# bop.net
KiCad netlist of a schematic drawn in EasyEDA Pro
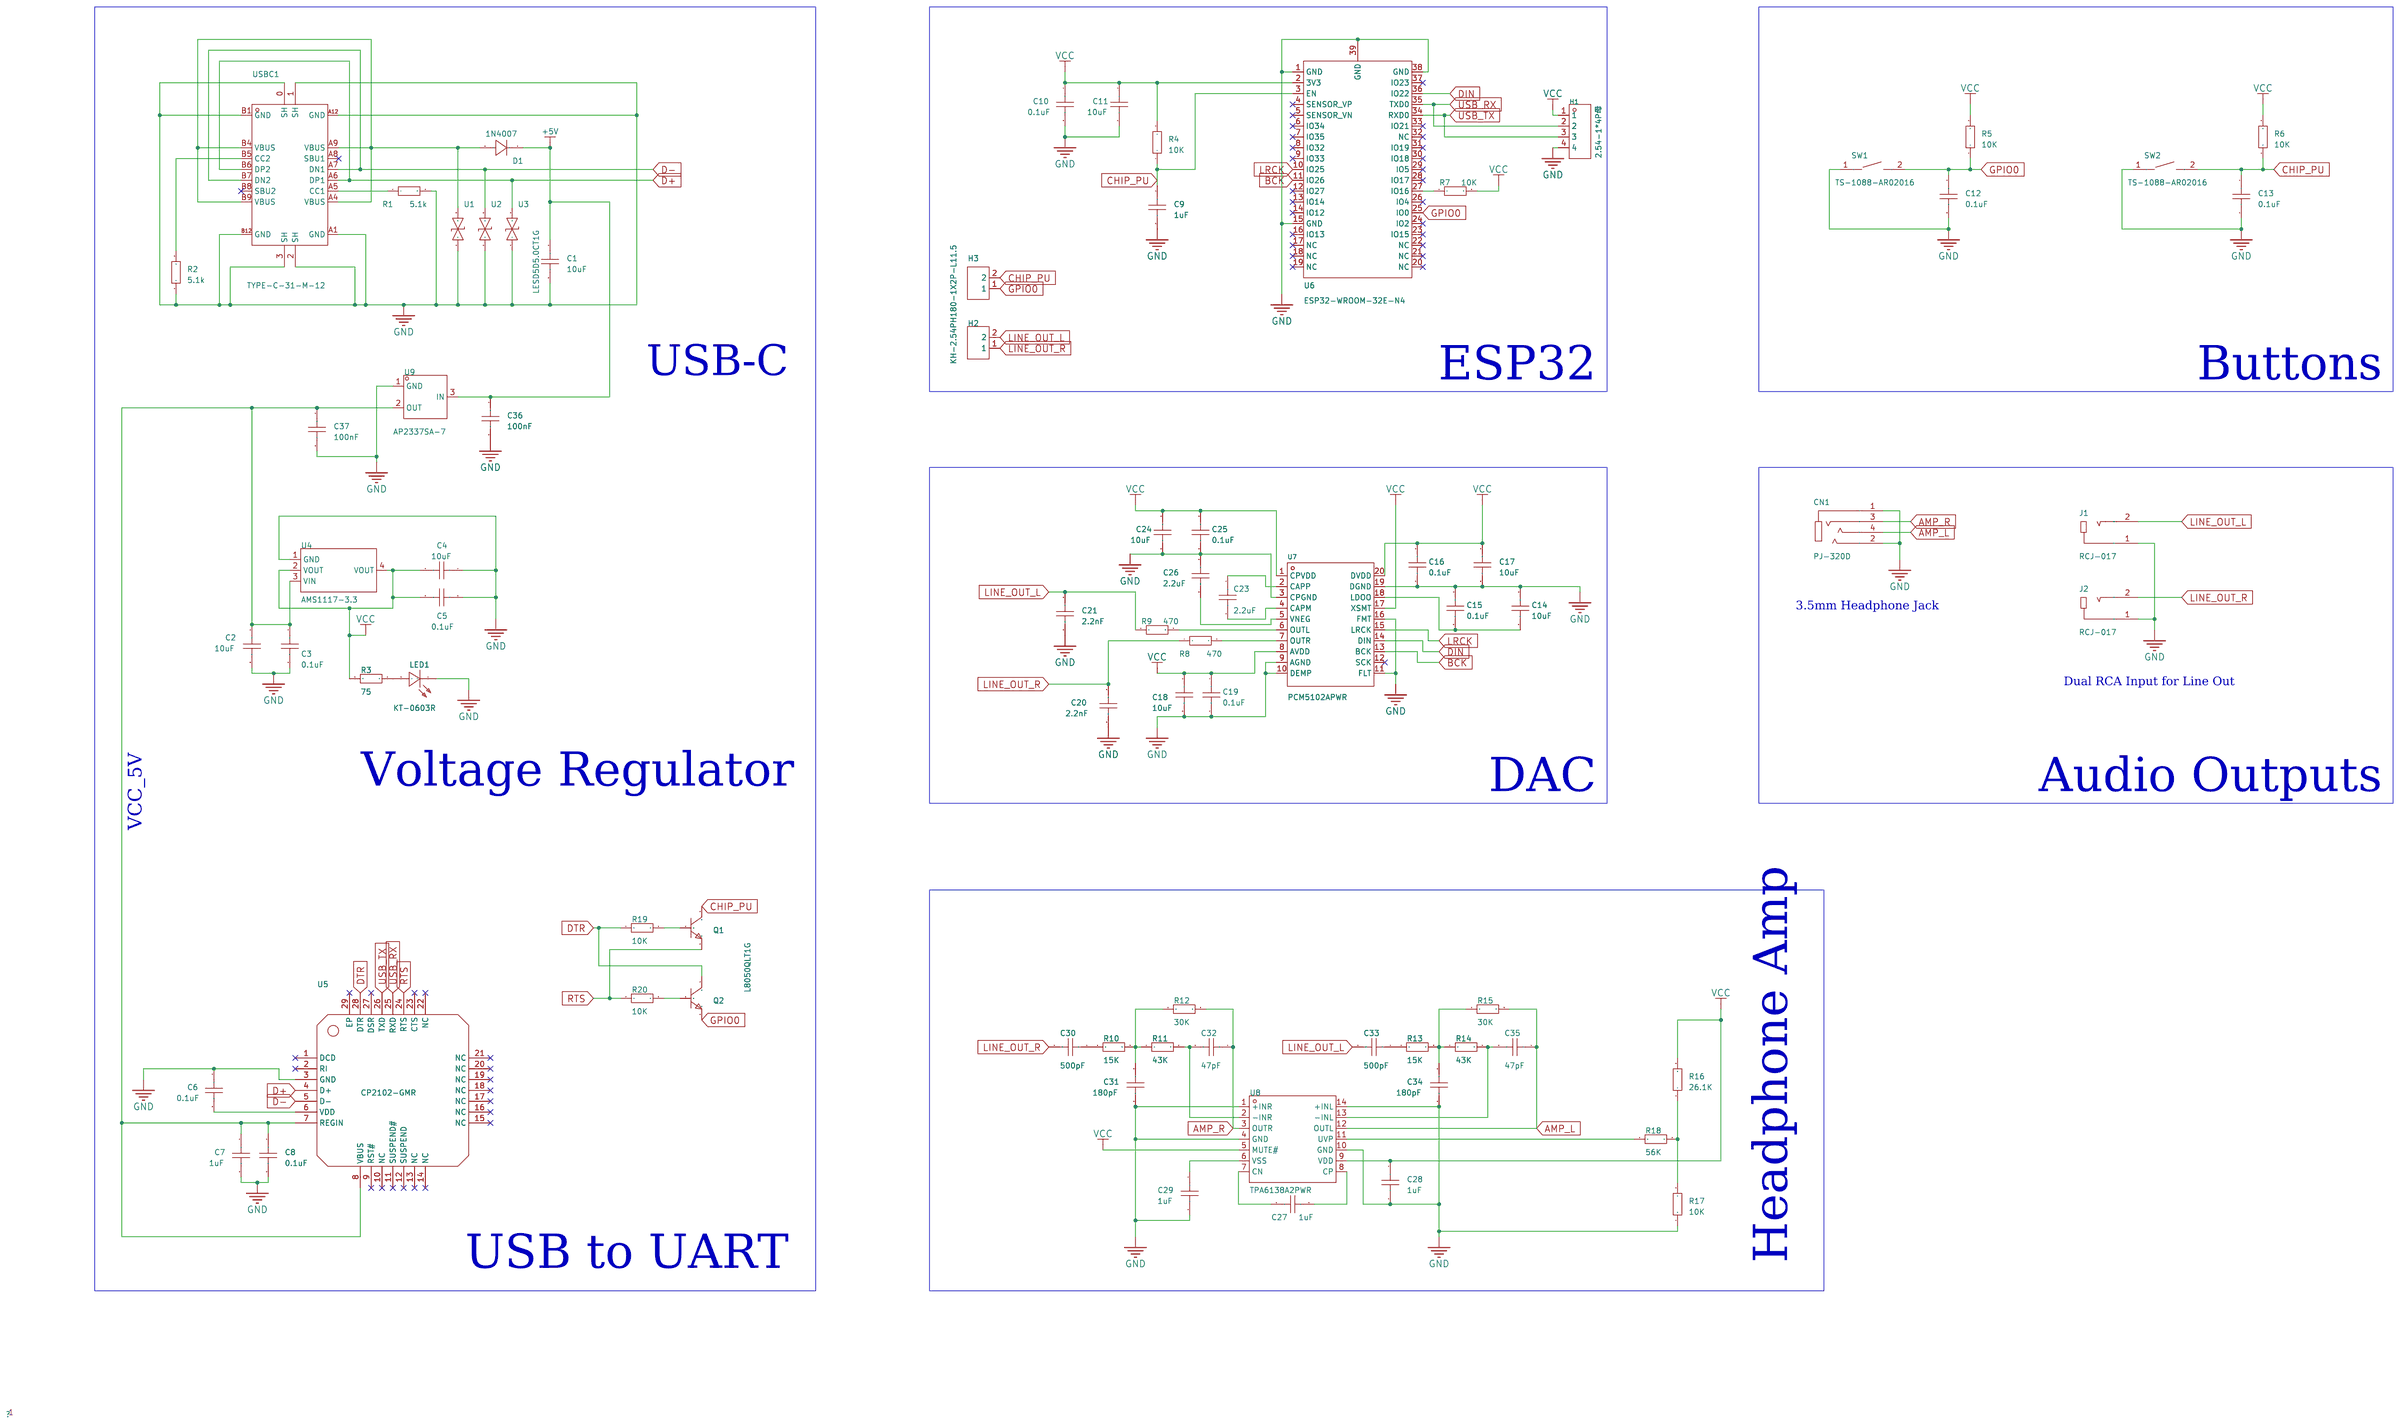
[diagram p0: schematic sheet]

(export (version "E")
  (design (tool "Eeschema 10.0.6"))
  (components
    (comp (ref "C1")
      (value "10uF")
      (footprint "easyedapro:C0603")
      (libsource (lib "easyedapro") (part "CAP"))
    )
    (comp (ref "C2")
      (value "10uF")
      (footprint "easyedapro:C0603")
      (libsource (lib "easyedapro") (part "CAP"))
    )
    (comp (ref "C3")
      (value "0.1uF")
      (footprint "easyedapro:C0603")
      (libsource (lib "easyedapro") (part "CAP"))
    )
    (comp (ref "C4")
      (value "10uF")
      (footprint "easyedapro:C0603")
      (libsource (lib "easyedapro") (part "CAP"))
    )
    (comp (ref "C5")
      (value "0.1uF")
      (footprint "easyedapro:C0603")
      (libsource (lib "easyedapro") (part "CAP"))
    )
    (comp (ref "C6")
      (value "0.1uF")
      (footprint "easyedapro:C0603")
      (libsource (lib "easyedapro") (part "CAP"))
    )
    (comp (ref "C7") (value "1uF") (footprint "easyedapro:C0603") (libsource (lib "easyedapro") (part "CAP")))
    (comp (ref "C8")
      (value "0.1uF")
      (footprint "easyedapro:C0603")
      (libsource (lib "easyedapro") (part "CAP"))
    )
    (comp (ref "C9") (value "1uF") (footprint "easyedapro:C0603") (libsource (lib "easyedapro") (part "CAP")))
    (comp (ref "C10")
      (value "0.1uF")
      (footprint "easyedapro:C0603")
      (libsource (lib "easyedapro") (part "CAP"))
    )
    (comp (ref "C11")
      (value "10uF")
      (footprint "easyedapro:C0603")
      (libsource (lib "easyedapro") (part "CAP"))
    )
    (comp (ref "C12")
      (value "0.1uF")
      (footprint "easyedapro:C0603")
      (libsource (lib "easyedapro") (part "CAP"))
    )
    (comp (ref "C13")
      (value "0.1uF")
      (footprint "easyedapro:C0603")
      (libsource (lib "easyedapro") (part "CAP"))
    )
    (comp (ref "C14")
      (value "10uF")
      (footprint "easyedapro:C0603")
      (libsource (lib "easyedapro") (part "CAP"))
    )
    (comp (ref "C15")
      (value "0.1uF")
      (footprint "easyedapro:C0603")
      (libsource (lib "easyedapro") (part "CAP"))
    )
    (comp (ref "C16")
      (value "0.1uF")
      (footprint "easyedapro:C0603")
      (libsource (lib "easyedapro") (part "CAP"))
    )
    (comp (ref "C17")
      (value "10uF")
      (footprint "easyedapro:C0603")
      (libsource (lib "easyedapro") (part "CAP"))
    )
    (comp (ref "C18")
      (value "10uF")
      (footprint "easyedapro:C0603")
      (libsource (lib "easyedapro") (part "CAP"))
    )
    (comp (ref "C19")
      (value "0.1uF")
      (footprint "easyedapro:C0603")
      (libsource (lib "easyedapro") (part "CAP"))
    )
    (comp (ref "C20")
      (value "2.2nF")
      (footprint "easyedapro:C0603")
      (libsource (lib "easyedapro") (part "CAP"))
    )
    (comp (ref "C21")
      (value "2.2nF")
      (footprint "easyedapro:C0603")
      (libsource (lib "easyedapro") (part "CAP"))
    )
    (comp (ref "C23")
      (value "2.2uF")
      (footprint "easyedapro:C0603")
      (libsource (lib "easyedapro") (part "CAP"))
    )
    (comp (ref "C24")
      (value "10uF")
      (footprint "easyedapro:C0603")
      (libsource (lib "easyedapro") (part "CAP"))
    )
    (comp (ref "C25")
      (value "0.1uF")
      (footprint "easyedapro:C0603")
      (libsource (lib "easyedapro") (part "CAP"))
    )
    (comp (ref "C26")
      (value "2.2uF")
      (footprint "easyedapro:C0603")
      (libsource (lib "easyedapro") (part "CAP"))
    )
    (comp (ref "C27")
      (value "1uF")
      (footprint "easyedapro:C0603")
      (libsource (lib "easyedapro") (part "CAP"))
    )
    (comp (ref "C28")
      (value "1uF")
      (footprint "easyedapro:C0603")
      (libsource (lib "easyedapro") (part "CAP"))
    )
    (comp (ref "C29")
      (value "1uF")
      (footprint "easyedapro:C0603")
      (libsource (lib "easyedapro") (part "CAP"))
    )
    (comp (ref "C30")
      (value "500pF")
      (footprint "easyedapro:C0603")
      (libsource (lib "easyedapro") (part "CAP"))
    )
    (comp (ref "C31")
      (value "180pF")
      (footprint "easyedapro:C0603")
      (libsource (lib "easyedapro") (part "CAP"))
    )
    (comp (ref "C32")
      (value "47pF")
      (footprint "easyedapro:C0603")
      (libsource (lib "easyedapro") (part "CAP"))
    )
    (comp (ref "C33")
      (value "500pF")
      (footprint "easyedapro:C0603")
      (libsource (lib "easyedapro") (part "CAP"))
    )
    (comp (ref "C34")
      (value "180pF")
      (footprint "easyedapro:C0603")
      (libsource (lib "easyedapro") (part "CAP"))
    )
    (comp (ref "C35")
      (value "47pF")
      (footprint "easyedapro:C0603")
      (libsource (lib "easyedapro") (part "CAP"))
    )
    (comp (ref "C36")
      (value "100nF")
      (footprint "easyedapro:C0603")
      (libsource (lib "easyedapro") (part "CAP"))
    )
    (comp (ref "C37")
      (value "100nF")
      (footprint "easyedapro:C0603")
      (libsource (lib "easyedapro") (part "CAP"))
    )
    (comp (ref "CN1")
      (value "PJ-320D")
      (footprint "easyedapro:AUDIO-SMD_PJ-320D")
      (fields (field (name "Manufacturer") "USAKRO(美韩)"))
      (libsource (lib "easyedapro") (part "PJ-320D_C521460"))
    )
    (comp (ref "D1")
      (value "1N4007")
      (footprint "easyedapro:SMA_L4.3-W2.5-LS5.0-RD")
      (fields (field (name "Manufacturer") "TWGMC(台湾迪嘉)"))
      (libsource (lib "easyedapro") (part "1N4007_C727081"))
    )
    (comp (ref "H1")
      (value "2.54-1*4P母")
      (footprint "easyedapro:HDR-TH_4P-P2.54-V-F")
      (fields (field (name "Manufacturer") "BOOMELE(博穆精密)"))
      (libsource (lib "easyedapro") (part "2.54-1*4P母"))
    )
    (comp (ref "H2")
      (value "KH-2.54PH180-1X2P-L11.5")
      (footprint "easyedapro:HDR-TH_2P-P2.54-V-M")
      (fields (field (name "Manufacturer") "kinghelm(金航标)"))
      (libsource (lib "easyedapro") (part "KH-2.54PH180-1X2P-L11.5"))
    )
    (comp (ref "H3")
      (value "KH-2.54PH180-1X2P-L11.5")
      (footprint "easyedapro:HDR-TH_2P-P2.54-V-M")
      (fields (field (name "Manufacturer") "kinghelm(金航标)"))
      (libsource (lib "easyedapro") (part "KH-2.54PH180-1X2P-L11.5"))
    )
    (comp (ref "J1")
      (value "RCJ-017")
      (footprint "easyedapro:CONN-TH_RCJ-013")
      (fields (field (name "Manufacturer") "CUI"))
      (libsource (lib "easyedapro") (part "RCJ-017"))
    )
    (comp (ref "J2")
      (value "RCJ-017")
      (footprint "easyedapro:CONN-TH_RCJ-013")
      (fields (field (name "Manufacturer") "CUI"))
      (libsource (lib "easyedapro") (part "RCJ-017"))
    )
    (comp (ref "LED1")
      (value "KT-0603R")
      (footprint "easyedapro:LED0603-RD")
      (fields (field (name "Manufacturer") "KENTO"))
      (libsource (lib "easyedapro") (part "KT-0603R"))
    )
    (comp (ref "Q1")
      (value "L8050QLT1G")
      (footprint "easyedapro:SOT-23-3_L2.9-W1.3-P1.90-LS2.4-BR")
      (fields (field (name "Manufacturer") "LRC(乐山无线电)"))
      (libsource (lib "easyedapro") (part "L8050QLT1G"))
    )
    (comp (ref "Q2")
      (value "L8050QLT1G")
      (footprint "easyedapro:SOT-23-3_L2.9-W1.3-P1.90-LS2.4-BR")
      (fields (field (name "Manufacturer") "LRC(乐山无线电)"))
      (libsource (lib "easyedapro") (part "L8050QLT1G"))
    )
    (comp (ref "R1")
      (value "5.1k")
      (footprint "easyedapro:R0603")
      (libsource (lib "easyedapro") (part "Res"))
    )
    (comp (ref "R2")
      (value "5.1k")
      (footprint "easyedapro:R0603")
      (libsource (lib "easyedapro") (part "Res"))
    )
    (comp (ref "R3") (value "75") (footprint "easyedapro:R0603") (libsource (lib "easyedapro") (part "Res")))
    (comp (ref "R4") (value "10K") (footprint "easyedapro:R0603") (libsource (lib "easyedapro") (part "Res")))
    (comp (ref "R5") (value "10K") (footprint "easyedapro:R0603") (libsource (lib "easyedapro") (part "Res")))
    (comp (ref "R6") (value "10K") (footprint "easyedapro:R0603") (libsource (lib "easyedapro") (part "Res")))
    (comp (ref "R7") (value "10K") (footprint "easyedapro:R0603") (libsource (lib "easyedapro") (part "Res")))
    (comp (ref "R8") (value "470") (footprint "easyedapro:R0603") (libsource (lib "easyedapro") (part "Res")))
    (comp (ref "R9") (value "470") (footprint "easyedapro:R0603") (libsource (lib "easyedapro") (part "Res")))
    (comp (ref "R10")
      (value "15K")
      (footprint "easyedapro:R0603")
      (libsource (lib "easyedapro") (part "Res"))
    )
    (comp (ref "R11")
      (value "43K")
      (footprint "easyedapro:R0603")
      (libsource (lib "easyedapro") (part "Res"))
    )
    (comp (ref "R12")
      (value "30K")
      (footprint "easyedapro:R0603")
      (libsource (lib "easyedapro") (part "Res"))
    )
    (comp (ref "R13")
      (value "15K")
      (footprint "easyedapro:R0603")
      (libsource (lib "easyedapro") (part "Res"))
    )
    (comp (ref "R14")
      (value "43K")
      (footprint "easyedapro:R0603")
      (libsource (lib "easyedapro") (part "Res"))
    )
    (comp (ref "R15")
      (value "30K")
      (footprint "easyedapro:R0603")
      (libsource (lib "easyedapro") (part "Res"))
    )
    (comp (ref "R16")
      (value "26.1K")
      (footprint "easyedapro:R0603")
      (libsource (lib "easyedapro") (part "Res"))
    )
    (comp (ref "R17")
      (value "10K")
      (footprint "easyedapro:R0603")
      (libsource (lib "easyedapro") (part "Res"))
    )
    (comp (ref "R18")
      (value "56K")
      (footprint "easyedapro:R0603")
      (libsource (lib "easyedapro") (part "Res"))
    )
    (comp (ref "R19")
      (value "10K")
      (footprint "easyedapro:R0603")
      (libsource (lib "easyedapro") (part "Res"))
    )
    (comp (ref "R20")
      (value "10K")
      (footprint "easyedapro:R0603")
      (libsource (lib "easyedapro") (part "Res"))
    )
    (comp (ref "SW1")
      (value "TS-1088-AR02016")
      (footprint "easyedapro:SW-SMD_L3.9-W3.0-P4.45")
      (fields (field (name "Manufacturer") "XUNPU(讯普)"))
      (libsource (lib "easyedapro") (part "TS-1088-AR02016"))
    )
    (comp (ref "SW2")
      (value "TS-1088-AR02016")
      (footprint "easyedapro:SW-SMD_L3.9-W3.0-P4.45")
      (fields (field (name "Manufacturer") "XUNPU(讯普)"))
      (libsource (lib "easyedapro") (part "TS-1088-AR02016"))
    )
    (comp (ref "U1")
      (value "LESD5D5.0CT1G")
      (footprint "easyedapro:SOD-523_L1.2-W0.8-LS1.6-BI")
      (fields (field (name "Manufacturer") "Leiditech(雷卯电子)"))
      (libsource (lib "easyedapro") (part "LESD5D5.0CT1G_C5246195"))
    )
    (comp (ref "U2")
      (value "LESD5D5.0CT1G")
      (footprint "easyedapro:SOD-523_L1.2-W0.8-LS1.6-BI")
      (fields (field (name "Manufacturer") "Leiditech(雷卯电子)"))
      (libsource (lib "easyedapro") (part "LESD5D5.0CT1G_C5246195"))
    )
    (comp (ref "U3")
      (value "LESD5D5.0CT1G")
      (footprint "easyedapro:SOD-523_L1.2-W0.8-LS1.6-BI")
      (fields (field (name "Manufacturer") "Leiditech(雷卯电子)"))
      (libsource (lib "easyedapro") (part "LESD5D5.0CT1G_C5246195"))
    )
    (comp (ref "U4")
      (value "AMS1117-3.3")
      (footprint "easyedapro:SOT-223-3_L6.5-W3.4-P2.30-LS7.0-BR")
      (fields (field (name "Manufacturer") "AMS"))
      (libsource (lib "easyedapro") (part "AMS1117-3.3"))
    )
    (comp (ref "U5")
      (value "CP2102-GMR")
      (footprint "easyedapro:WQFN-28_L5.0-W5.0-P0.50-BL-EP3.2")
      (fields (field (name "Manufacturer") "SKYWORKS/SILICON LABS(芯科)"))
      (libsource (lib "easyedapro") (part "CP2102-GMR"))
    )
    (comp (ref "U6")
      (value "ESP32-WROOM-32E-N4")
      (footprint "easyedapro:WIFI-SMD_ESP32-WROOM-32E")
      (fields (field (name "Manufacturer") "ESPRESSIF(乐鑫)"))
      (libsource (lib "easyedapro") (part "ESP32-WROOM-32E(4MB)"))
    )
    (comp (ref "U7")
      (value "PCM5102APWR")
      (footprint "easyedapro:TSSOP-20_L6.5-W4.4-P0.65-LS6.4-BL")
      (fields (field (name "Manufacturer") "TI(德州仪器)"))
      (libsource (lib "easyedapro") (part "PCM5102APWR"))
    )
    (comp (ref "U8")
      (value "TPA6138A2PWR")
      (footprint "easyedapro:TSSOP-14_L5.0-W4.4-P0.65-LS6.4-BL")
      (fields (field (name "Manufacturer") "TI(德州仪器)"))
      (libsource (lib "easyedapro") (part "TPA6138A2PWR"))
    )
    (comp (ref "U9")
      (value "AP2337SA-7")
      (footprint "easyedapro:SOT-23-3_L2.9-W1.3-P1.90-LS2.4-BR")
      (fields (field (name "Manufacturer") "DIODES(美台)"))
      (libsource (lib "easyedapro") (part "AP2337SA-7"))
    )
    (comp (ref "USBC1")
      (value "TYPE-C-31-M-12")
      (footprint "easyedapro:USB-C_SMD-TYPE-C-31-M-12")
      (fields (field (name "Manufacturer") "韩国韩荣"))
      (libsource (lib "easyedapro") (part "TYPE-C-31-M-12"))
    )
  )
  (nets
    (net (code "1") (name "+5V") (class "Default")
      (node (ref "C1") (pin "1") (pinfunction "1_1") (pintype "input"))
      (node (ref "C36") (pin "1") (pinfunction "1_1") (pintype "input"))
      (node (ref "D1") (pin "1") (pinfunction "K_1") (pintype "unspecified"))
      (node (ref "U9") (pin "3") (pinfunction "IN_3") (pintype "input"))
    )
    (net (code "2") (name "AMP_L") (class "Default")
      (node (ref "C35") (pin "1") (pinfunction "1_1") (pintype "input"))
      (node (ref "CN1") (pin "4") (pinfunction "4_4") (pintype "input"))
      (node (ref "R15") (pin "2") (pinfunction "2_2") (pintype "input"))
      (node (ref "U8") (pin "12") (pinfunction "OUTL_12") (pintype "unspecified"))
    )
    (net (code "3") (name "AMP_R") (class "Default")
      (node (ref "C32") (pin "1") (pinfunction "1_1") (pintype "input"))
      (node (ref "CN1") (pin "3") (pinfunction "3_3") (pintype "input"))
      (node (ref "R12") (pin "2") (pinfunction "2_2") (pintype "input"))
      (node (ref "U8") (pin "3") (pinfunction "OUTR_3") (pintype "unspecified"))
    )
    (net (code "4") (name "BCK") (class "Default")
      (node (ref "U6") (pin "11") (pinfunction "IO26_11") (pintype "unspecified"))
      (node (ref "U7") (pin "13") (pinfunction "BCK_13") (pintype "input"))
    )
    (net (code "5") (name "CHIP_PU") (class "Default")
      (node (ref "C13") (pin "1") (pinfunction "1_1") (pintype "input"))
      (node (ref "C9") (pin "1") (pinfunction "1_1") (pintype "input"))
      (node (ref "H3") (pin "2") (pinfunction "2_2") (pintype "unspecified"))
      (node (ref "Q1") (pin "3") (pinfunction "C_3") (pintype "unspecified"))
      (node (ref "R4") (pin "1") (pinfunction "1_1") (pintype "input"))
      (node (ref "R6") (pin "1") (pinfunction "1_1") (pintype "input"))
      (node (ref "SW2") (pin "2") (pinfunction "2_2") (pintype "unspecified"))
      (node (ref "U6") (pin "3") (pinfunction "EN_3") (pintype "unspecified"))
    )
    (net (code "6") (name "D+") (class "Default")
      (node (ref "U3") (pin "2") (pinfunction "2_2") (pintype "unspecified"))
      (node (ref "U5") (pin "4") (pinfunction "D+_4") (pintype "unspecified"))
      (node (ref "USBC1") (pin "A6") (pinfunction "DP1_A6") (pintype "unspecified"))
      (node (ref "USBC1") (pin "B6") (pinfunction "DP2_B6") (pintype "unspecified"))
    )
    (net (code "7") (name "D-") (class "Default")
      (node (ref "U2") (pin "2") (pinfunction "2_2") (pintype "unspecified"))
      (node (ref "U5") (pin "5") (pinfunction "D-_5") (pintype "unspecified"))
      (node (ref "USBC1") (pin "A7") (pinfunction "DN1_A7") (pintype "unspecified"))
      (node (ref "USBC1") (pin "B7") (pinfunction "DN2_B7") (pintype "unspecified"))
    )
    (net (code "8") (name "DIN") (class "Default")
      (node (ref "U6") (pin "36") (pinfunction "IO22_36") (pintype "unspecified"))
      (node (ref "U7") (pin "14") (pinfunction "DIN_14") (pintype "input"))
    )
    (net (code "9") (name "DTR") (class "Default")
      (node (ref "Q2") (pin "3") (pinfunction "C_3") (pintype "unspecified"))
      (node (ref "R19") (pin "1") (pinfunction "1_1") (pintype "input"))
      (node (ref "U5") (pin "28") (pinfunction "DTR_28") (pintype "unspecified"))
    )
    (net (code "10") (name "GND") (class "Default")
      (node (ref "C1") (pin "2") (pinfunction "2_2") (pintype "input"))
      (node (ref "C10") (pin "2") (pinfunction "2_2") (pintype "input"))
      (node (ref "C11") (pin "2") (pinfunction "2_2") (pintype "input"))
      (node (ref "C12") (pin "2") (pinfunction "2_2") (pintype "input"))
      (node (ref "C13") (pin "2") (pinfunction "2_2") (pintype "input"))
      (node (ref "C14") (pin "1") (pinfunction "1_1") (pintype "input"))
      (node (ref "C15") (pin "1") (pinfunction "1_1") (pintype "input"))
      (node (ref "C16") (pin "2") (pinfunction "2_2") (pintype "input"))
      (node (ref "C17") (pin "2") (pinfunction "2_2") (pintype "input"))
      (node (ref "C18") (pin "2") (pinfunction "2_2") (pintype "input"))
      (node (ref "C19") (pin "2") (pinfunction "2_2") (pintype "input"))
      (node (ref "C2") (pin "2") (pinfunction "2_2") (pintype "input"))
      (node (ref "C20") (pin "2") (pinfunction "2_2") (pintype "input"))
      (node (ref "C21") (pin "2") (pinfunction "2_2") (pintype "input"))
      (node (ref "C24") (pin "2") (pinfunction "2_2") (pintype "input"))
      (node (ref "C25") (pin "2") (pinfunction "2_2") (pintype "input"))
      (node (ref "C26") (pin "1") (pinfunction "1_1") (pintype "input"))
      (node (ref "C28") (pin "2") (pinfunction "2_2") (pintype "input"))
      (node (ref "C29") (pin "2") (pinfunction "2_2") (pintype "input"))
      (node (ref "C3") (pin "2") (pinfunction "2_2") (pintype "input"))
      (node (ref "C31") (pin "2") (pinfunction "2_2") (pintype "input"))
      (node (ref "C34") (pin "2") (pinfunction "2_2") (pintype "input"))
      (node (ref "C36") (pin "2") (pinfunction "2_2") (pintype "input"))
      (node (ref "C37") (pin "2") (pinfunction "2_2") (pintype "input"))
      (node (ref "C4") (pin "1") (pinfunction "1_1") (pintype "input"))
      (node (ref "C5") (pin "1") (pinfunction "1_1") (pintype "input"))
      (node (ref "C6") (pin "1") (pinfunction "1_1") (pintype "input"))
      (node (ref "C7") (pin "2") (pinfunction "2_2") (pintype "input"))
      (node (ref "C8") (pin "2") (pinfunction "2_2") (pintype "input"))
      (node (ref "C9") (pin "2") (pinfunction "2_2") (pintype "input"))
      (node (ref "CN1") (pin "1") (pinfunction "1_1") (pintype "input"))
      (node (ref "CN1") (pin "2") (pinfunction "2_2") (pintype "input"))
      (node (ref "H1") (pin "4") (pinfunction "4_4") (pintype "input"))
      (node (ref "J1") (pin "1") (pinfunction "1_1") (pintype "unspecified"))
      (node (ref "J2") (pin "1") (pinfunction "1_1") (pintype "unspecified"))
      (node (ref "LED1") (pin "1") (pinfunction "K_1") (pintype "unspecified"))
      (node (ref "R1") (pin "2") (pinfunction "2_2") (pintype "input"))
      (node (ref "R17") (pin "1") (pinfunction "1_1") (pintype "input"))
      (node (ref "R2") (pin "1") (pinfunction "1_1") (pintype "input"))
      (node (ref "SW1") (pin "1") (pinfunction "1_1") (pintype "unspecified"))
      (node (ref "SW2") (pin "1") (pinfunction "1_1") (pintype "unspecified"))
      (node (ref "U1") (pin "1") (pinfunction "1_1") (pintype "unspecified"))
      (node (ref "U2") (pin "1") (pinfunction "1_1") (pintype "unspecified"))
      (node (ref "U3") (pin "1") (pinfunction "1_1") (pintype "unspecified"))
      (node (ref "U4") (pin "1") (pinfunction "GND_1") (pintype "unspecified"))
      (node (ref "U5") (pin "3") (pinfunction "GND_3") (pintype "unspecified"))
      (node (ref "U6") (pin "1") (pinfunction "GND_1") (pintype "unspecified"))
      (node (ref "U6") (pin "15") (pinfunction "GND_15") (pintype "unspecified"))
      (node (ref "U6") (pin "38") (pinfunction "GND_38") (pintype "unspecified"))
      (node (ref "U6") (pin "39") (pinfunction "GND_39") (pintype "unspecified"))
      (node (ref "U7") (pin "10") (pinfunction "DEMP_10") (pintype "input"))
      (node (ref "U7") (pin "11") (pinfunction "FLT_11") (pintype "input"))
      (node (ref "U7") (pin "16") (pinfunction "FMT_16") (pintype "input"))
      (node (ref "U7") (pin "19") (pinfunction "DGND_19") (pintype "input"))
      (node (ref "U7") (pin "3") (pinfunction "CPGND_3") (pintype "input"))
      (node (ref "U7") (pin "9") (pinfunction "AGND_9") (pintype "input"))
      (node (ref "U8") (pin "1") (pinfunction "+INR_1") (pintype "unspecified"))
      (node (ref "U8") (pin "10") (pinfunction "GND_10") (pintype "unspecified"))
      (node (ref "U8") (pin "14") (pinfunction "+INL_14") (pintype "unspecified"))
      (node (ref "U8") (pin "4") (pinfunction "GND_4") (pintype "unspecified"))
      (node (ref "U9") (pin "1") (pinfunction "GND_1") (pintype "input"))
      (node (ref "USBC1") (pin "0") (pinfunction "SH_0") (pintype "unspecified"))
      (node (ref "USBC1") (pin "1") (pinfunction "SH_1") (pintype "unspecified"))
      (node (ref "USBC1") (pin "2") (pinfunction "SH_2") (pintype "unspecified"))
      (node (ref "USBC1") (pin "3") (pinfunction "SH_3") (pintype "unspecified"))
      (node (ref "USBC1") (pin "A1") (pinfunction "GND_A1") (pintype "unspecified"))
      (node (ref "USBC1") (pin "A12") (pinfunction "GND_A12") (pintype "unspecified"))
      (node (ref "USBC1") (pin "B1") (pinfunction "GND_B1") (pintype "unspecified"))
      (node (ref "USBC1") (pin "B12") (pinfunction "GND_B12") (pintype "unspecified"))
    )
    (net (code "11") (name "GPIO0") (class "Default")
      (node (ref "C12") (pin "1") (pinfunction "1_1") (pintype "input"))
      (node (ref "H3") (pin "1") (pinfunction "1_1") (pintype "unspecified"))
      (node (ref "Q2") (pin "2") (pinfunction "E_2") (pintype "unspecified"))
      (node (ref "R5") (pin "1") (pinfunction "1_1") (pintype "input"))
      (node (ref "SW1") (pin "2") (pinfunction "2_2") (pintype "unspecified"))
      (node (ref "U6") (pin "25") (pinfunction "IO0_25") (pintype "unspecified"))
    )
    (net (code "12") (name "LINE_OUT_L") (class "Default")
      (node (ref "C21") (pin "1") (pinfunction "1_1") (pintype "input"))
      (node (ref "C33") (pin "2") (pinfunction "2_2") (pintype "input"))
      (node (ref "H2") (pin "2") (pinfunction "2_2") (pintype "unspecified"))
      (node (ref "J1") (pin "2") (pinfunction "2_2") (pintype "unspecified"))
      (node (ref "R9") (pin "1") (pinfunction "1_1") (pintype "input"))
    )
    (net (code "13") (name "LINE_OUT_R") (class "Default")
      (node (ref "C20") (pin "1") (pinfunction "1_1") (pintype "input"))
      (node (ref "C30") (pin "2") (pinfunction "2_2") (pintype "input"))
      (node (ref "H2") (pin "1") (pinfunction "1_1") (pintype "unspecified"))
      (node (ref "J2") (pin "2") (pinfunction "2_2") (pintype "unspecified"))
      (node (ref "R8") (pin "1") (pinfunction "1_1") (pintype "input"))
    )
    (net (code "14") (name "LRCK") (class "Default")
      (node (ref "U6") (pin "10") (pinfunction "IO25_10") (pintype "unspecified"))
      (node (ref "U7") (pin "15") (pinfunction "LRCK_15") (pintype "input"))
    )
    (net (code "15") (name "Net-(C30-Pad1)") (class "Default")
      (node (ref "C30") (pin "1") (pinfunction "1_1") (pintype "input"))
      (node (ref "R10") (pin "1") (pinfunction "1_1") (pintype "input"))
    )
    (net (code "16") (name "Net-(C31-Pad1)") (class "Default")
      (node (ref "C31") (pin "1") (pinfunction "1_1") (pintype "input"))
      (node (ref "R10") (pin "2") (pinfunction "2_2") (pintype "input"))
      (node (ref "R11") (pin "1") (pinfunction "1_1") (pintype "input"))
      (node (ref "R12") (pin "1") (pinfunction "1_1") (pintype "input"))
    )
    (net (code "17") (name "Net-(C33-Pad1)") (class "Default")
      (node (ref "C33") (pin "1") (pinfunction "1_1") (pintype "input"))
      (node (ref "R13") (pin "1") (pinfunction "1_1") (pintype "input"))
    )
    (net (code "18") (name "Net-(C34-Pad1)") (class "Default")
      (node (ref "C34") (pin "1") (pinfunction "1_1") (pintype "input"))
      (node (ref "R13") (pin "2") (pinfunction "2_2") (pintype "input"))
      (node (ref "R14") (pin "1") (pinfunction "1_1") (pintype "input"))
      (node (ref "R15") (pin "1") (pinfunction "1_1") (pintype "input"))
    )
    (net (code "19") (name "Net-(D1-A)") (class "Default")
      (node (ref "D1") (pin "2") (pinfunction "A_2") (pintype "unspecified"))
      (node (ref "U1") (pin "2") (pinfunction "2_2") (pintype "unspecified"))
      (node (ref "USBC1") (pin "A4") (pinfunction "VBUS_A4") (pintype "unspecified"))
      (node (ref "USBC1") (pin "A9") (pinfunction "VBUS_A9") (pintype "unspecified"))
      (node (ref "USBC1") (pin "B4") (pinfunction "VBUS_B4") (pintype "unspecified"))
      (node (ref "USBC1") (pin "B9") (pinfunction "VBUS_B9") (pintype "unspecified"))
    )
    (net (code "20") (name "Net-(LED1-A)") (class "Default")
      (node (ref "LED1") (pin "2") (pinfunction "A_2") (pintype "unspecified"))
      (node (ref "R3") (pin "1") (pinfunction "1_1") (pintype "input"))
    )
    (net (code "21") (name "Net-(Q1-B)") (class "Default")
      (node (ref "Q1") (pin "1") (pinfunction "B_1") (pintype "unspecified"))
      (node (ref "R19") (pin "2") (pinfunction "2_2") (pintype "input"))
    )
    (net (code "22") (name "Net-(Q2-B)") (class "Default")
      (node (ref "Q2") (pin "1") (pinfunction "B_1") (pintype "unspecified"))
      (node (ref "R20") (pin "2") (pinfunction "2_2") (pintype "input"))
    )
    (net (code "23") (name "Net-(R16-Pad1)") (class "Default")
      (node (ref "R16") (pin "1") (pinfunction "1_1") (pintype "input"))
      (node (ref "R17") (pin "2") (pinfunction "2_2") (pintype "input"))
      (node (ref "R18") (pin "2") (pinfunction "2_2") (pintype "input"))
    )
    (net (code "24") (name "Net-(U4-VIN)") (class "Default")
      (node (ref "C2") (pin "1") (pinfunction "1_1") (pintype "input"))
      (node (ref "C3") (pin "1") (pinfunction "1_1") (pintype "input"))
      (node (ref "C37") (pin "1") (pinfunction "1_1") (pintype "input"))
      (node (ref "C7") (pin "1") (pinfunction "1_1") (pintype "input"))
      (node (ref "C8") (pin "1") (pinfunction "1_1") (pintype "input"))
      (node (ref "U4") (pin "3") (pinfunction "VIN_3") (pintype "unspecified"))
      (node (ref "U5") (pin "7") (pinfunction "REGIN_7") (pintype "unspecified"))
      (node (ref "U5") (pin "8") (pinfunction "VBUS_8") (pintype "unspecified"))
      (node (ref "U9") (pin "2") (pinfunction "OUT_2") (pintype "input"))
    )
    (net (code "25") (name "Net-(U5-VDD)") (class "Default")
      (node (ref "C6") (pin "2") (pinfunction "2_2") (pintype "input"))
      (node (ref "U5") (pin "6") (pinfunction "VDD_6") (pintype "unspecified"))
    )
    (net (code "26") (name "Net-(U6-IO16)") (class "Default")
      (node (ref "R7") (pin "1") (pinfunction "1_1") (pintype "input"))
      (node (ref "U6") (pin "27") (pinfunction "IO16_27") (pintype "unspecified"))
    )
    (net (code "27") (name "Net-(U7-CAPM)") (class "Default")
      (node (ref "C23") (pin "2") (pinfunction "2_2") (pintype "input"))
      (node (ref "U7") (pin "4") (pinfunction "CAPM_4") (pintype "input"))
    )
    (net (code "28") (name "Net-(U7-CAPP)") (class "Default")
      (node (ref "C23") (pin "1") (pinfunction "1_1") (pintype "input"))
      (node (ref "U7") (pin "2") (pinfunction "CAPP_2") (pintype "input"))
    )
    (net (code "29") (name "Net-(U7-LDOO)") (class "Default")
      (node (ref "C14") (pin "2") (pinfunction "2_2") (pintype "input"))
      (node (ref "C15") (pin "2") (pinfunction "2_2") (pintype "input"))
      (node (ref "U7") (pin "18") (pinfunction "LDOO_18") (pintype "input"))
    )
    (net (code "30") (name "Net-(U7-OUTL)") (class "Default")
      (node (ref "R9") (pin "2") (pinfunction "2_2") (pintype "input"))
      (node (ref "U7") (pin "6") (pinfunction "OUTL_6") (pintype "input"))
    )
    (net (code "31") (name "Net-(U7-OUTR)") (class "Default")
      (node (ref "R8") (pin "2") (pinfunction "2_2") (pintype "input"))
      (node (ref "U7") (pin "7") (pinfunction "OUTR_7") (pintype "input"))
    )
    (net (code "32") (name "Net-(U7-VNEG)") (class "Default")
      (node (ref "C26") (pin "2") (pinfunction "2_2") (pintype "input"))
      (node (ref "U7") (pin "5") (pinfunction "VNEG_5") (pintype "input"))
    )
    (net (code "33") (name "Net-(U8--INL)") (class "Default")
      (node (ref "C35") (pin "2") (pinfunction "2_2") (pintype "input"))
      (node (ref "R14") (pin "2") (pinfunction "2_2") (pintype "input"))
      (node (ref "U8") (pin "13") (pinfunction "-INL_13") (pintype "unspecified"))
    )
    (net (code "34") (name "Net-(U8--INR)") (class "Default")
      (node (ref "C32") (pin "2") (pinfunction "2_2") (pintype "input"))
      (node (ref "R11") (pin "2") (pinfunction "2_2") (pintype "input"))
      (node (ref "U8") (pin "2") (pinfunction "-INR_2") (pintype "unspecified"))
    )
    (net (code "35") (name "Net-(U8-CN)") (class "Default")
      (node (ref "C27") (pin "2") (pinfunction "2_2") (pintype "input"))
      (node (ref "U8") (pin "7") (pinfunction "CN_7") (pintype "unspecified"))
    )
    (net (code "36") (name "Net-(U8-CP)") (class "Default")
      (node (ref "C27") (pin "1") (pinfunction "1_1") (pintype "input"))
      (node (ref "U8") (pin "8") (pinfunction "CP_8") (pintype "unspecified"))
    )
    (net (code "37") (name "Net-(U8-UVP)") (class "Default")
      (node (ref "R18") (pin "1") (pinfunction "1_1") (pintype "input"))
      (node (ref "U8") (pin "11") (pinfunction "UVP_11") (pintype "unspecified"))
    )
    (net (code "38") (name "Net-(U8-VSS)") (class "Default")
      (node (ref "C29") (pin "1") (pinfunction "1_1") (pintype "input"))
      (node (ref "U8") (pin "6") (pinfunction "VSS_6") (pintype "unspecified"))
    )
    (net (code "39") (name "Net-(USBC1-CC1)") (class "Default")
      (node (ref "R1") (pin "1") (pinfunction "1_1") (pintype "input"))
      (node (ref "USBC1") (pin "A5") (pinfunction "CC1_A5") (pintype "unspecified"))
    )
    (net (code "40") (name "Net-(USBC1-CC2)") (class "Default")
      (node (ref "R2") (pin "2") (pinfunction "2_2") (pintype "input"))
      (node (ref "USBC1") (pin "B5") (pinfunction "CC2_B5") (pintype "unspecified"))
    )
    (net (code "41") (name "RTS") (class "Default")
      (node (ref "Q1") (pin "2") (pinfunction "E_2") (pintype "unspecified"))
      (node (ref "R20") (pin "1") (pinfunction "1_1") (pintype "input"))
      (node (ref "U5") (pin "24") (pinfunction "RTS_24") (pintype "unspecified"))
    )
    (net (code "42") (name "USB_RX") (class "Default")
      (node (ref "H1") (pin "2") (pinfunction "2_2") (pintype "input"))
      (node (ref "U5") (pin "25") (pinfunction "RXD_25") (pintype "unspecified"))
      (node (ref "U6") (pin "35") (pinfunction "TXD0_35") (pintype "unspecified"))
    )
    (net (code "43") (name "USB_TX") (class "Default")
      (node (ref "H1") (pin "3") (pinfunction "3_3") (pintype "input"))
      (node (ref "U5") (pin "26") (pinfunction "TXD_26") (pintype "unspecified"))
      (node (ref "U6") (pin "34") (pinfunction "RXD0_34") (pintype "unspecified"))
    )
    (net (code "44") (name "VCC") (class "Default")
      (node (ref "C10") (pin "1") (pinfunction "1_1") (pintype "input"))
      (node (ref "C11") (pin "1") (pinfunction "1_1") (pintype "input"))
      (node (ref "C16") (pin "1") (pinfunction "1_1") (pintype "input"))
      (node (ref "C17") (pin "1") (pinfunction "1_1") (pintype "input"))
      (node (ref "C18") (pin "1") (pinfunction "1_1") (pintype "input"))
      (node (ref "C19") (pin "1") (pinfunction "1_1") (pintype "input"))
      (node (ref "C24") (pin "1") (pinfunction "1_1") (pintype "input"))
      (node (ref "C25") (pin "1") (pinfunction "1_1") (pintype "input"))
      (node (ref "C28") (pin "1") (pinfunction "1_1") (pintype "input"))
      (node (ref "C4") (pin "2") (pinfunction "2_2") (pintype "input"))
      (node (ref "C5") (pin "2") (pinfunction "2_2") (pintype "input"))
      (node (ref "H1") (pin "1") (pinfunction "1_1") (pintype "input"))
      (node (ref "R16") (pin "2") (pinfunction "2_2") (pintype "input"))
      (node (ref "R3") (pin "2") (pinfunction "2_2") (pintype "input"))
      (node (ref "R4") (pin "2") (pinfunction "2_2") (pintype "input"))
      (node (ref "R5") (pin "2") (pinfunction "2_2") (pintype "input"))
      (node (ref "R6") (pin "2") (pinfunction "2_2") (pintype "input"))
      (node (ref "R7") (pin "2") (pinfunction "2_2") (pintype "input"))
      (node (ref "U4") (pin "2") (pinfunction "VOUT_2") (pintype "unspecified"))
      (node (ref "U4") (pin "4") (pinfunction "VOUT_4") (pintype "unspecified"))
      (node (ref "U6") (pin "2") (pinfunction "3V3_2") (pintype "unspecified"))
      (node (ref "U7") (pin "1") (pinfunction "CPVDD_1") (pintype "input"))
      (node (ref "U7") (pin "17") (pinfunction "XSMT_17") (pintype "input"))
      (node (ref "U7") (pin "20") (pinfunction "DVDD_20") (pintype "input"))
      (node (ref "U7") (pin "8") (pinfunction "AVDD_8") (pintype "input"))
      (node (ref "U8") (pin "5") (pinfunction "MUTE#_5") (pintype "unspecified"))
      (node (ref "U8") (pin "9") (pinfunction "VDD_9") (pintype "unspecified"))
    )
    (net (code "45") (name "unconnected-(U5-CTS-Pad23)") (class "Default")
      (node (ref "U5") (pin "23") (pinfunction "CTS_23") (pintype "unspecified+no_connect"))
    )
    (net (code "46") (name "unconnected-(U5-DCD-Pad1)") (class "Default")
      (node (ref "U5") (pin "1") (pinfunction "DCD_1") (pintype "unspecified+no_connect"))
    )
    (net (code "47") (name "unconnected-(U5-DSR-Pad27)") (class "Default")
      (node (ref "U5") (pin "27") (pinfunction "DSR_27") (pintype "unspecified+no_connect"))
    )
    (net (code "48") (name "unconnected-(U5-EP-Pad29)") (class "Default")
      (node (ref "U5") (pin "29") (pinfunction "EP_29") (pintype "unspecified+no_connect"))
    )
    (net (code "49") (name "unconnected-(U5-NC-Pad10)") (class "Default")
      (node (ref "U5") (pin "10") (pinfunction "NC_10") (pintype "unspecified+no_connect"))
    )
    (net (code "50") (name "unconnected-(U5-NC-Pad13)") (class "Default")
      (node (ref "U5") (pin "13") (pinfunction "NC_13") (pintype "unspecified+no_connect"))
    )
    (net (code "51") (name "unconnected-(U5-NC-Pad14)") (class "Default")
      (node (ref "U5") (pin "14") (pinfunction "NC_14") (pintype "unspecified+no_connect"))
    )
    (net (code "52") (name "unconnected-(U5-NC-Pad15)") (class "Default")
      (node (ref "U5") (pin "15") (pinfunction "NC_15") (pintype "unspecified+no_connect"))
    )
    (net (code "53") (name "unconnected-(U5-NC-Pad16)") (class "Default")
      (node (ref "U5") (pin "16") (pinfunction "NC_16") (pintype "unspecified+no_connect"))
    )
    (net (code "54") (name "unconnected-(U5-NC-Pad17)") (class "Default")
      (node (ref "U5") (pin "17") (pinfunction "NC_17") (pintype "unspecified+no_connect"))
    )
    (net (code "55") (name "unconnected-(U5-NC-Pad18)") (class "Default")
      (node (ref "U5") (pin "18") (pinfunction "NC_18") (pintype "unspecified+no_connect"))
    )
    (net (code "56") (name "unconnected-(U5-NC-Pad19)") (class "Default")
      (node (ref "U5") (pin "19") (pinfunction "NC_19") (pintype "unspecified+no_connect"))
    )
    (net (code "57") (name "unconnected-(U5-NC-Pad20)") (class "Default")
      (node (ref "U5") (pin "20") (pinfunction "NC_20") (pintype "unspecified+no_connect"))
    )
    (net (code "58") (name "unconnected-(U5-NC-Pad21)") (class "Default")
      (node (ref "U5") (pin "21") (pinfunction "NC_21") (pintype "unspecified+no_connect"))
    )
    (net (code "59") (name "unconnected-(U5-NC-Pad22)") (class "Default")
      (node (ref "U5") (pin "22") (pinfunction "NC_22") (pintype "unspecified+no_connect"))
    )
    (net (code "60") (name "unconnected-(U5-RI-Pad2)") (class "Default")
      (node (ref "U5") (pin "2") (pinfunction "RI_2") (pintype "unspecified+no_connect"))
    )
    (net (code "61") (name "unconnected-(U5-RST#-Pad9)") (class "Default")
      (node (ref "U5") (pin "9") (pinfunction "RST#_9") (pintype "unspecified+no_connect"))
    )
    (net (code "62") (name "unconnected-(U5-SUSPEND#-Pad11)") (class "Default")
      (node (ref "U5") (pin "11") (pinfunction "SUSPEND#_11") (pintype "unspecified+no_connect"))
    )
    (net (code "63") (name "unconnected-(U5-SUSPEND-Pad12)") (class "Default")
      (node (ref "U5") (pin "12") (pinfunction "SUSPEND_12") (pintype "unspecified+no_connect"))
    )
    (net (code "64") (name "unconnected-(U6-IO2-Pad24)") (class "Default")
      (node (ref "U6") (pin "24") (pinfunction "IO2_24") (pintype "unspecified+no_connect"))
    )
    (net (code "65") (name "unconnected-(U6-IO4-Pad26)") (class "Default")
      (node (ref "U6") (pin "26") (pinfunction "IO4_26") (pintype "unspecified+no_connect"))
    )
    (net (code "66") (name "unconnected-(U6-IO5-Pad29)") (class "Default")
      (node (ref "U6") (pin "29") (pinfunction "IO5_29") (pintype "unspecified+no_connect"))
    )
    (net (code "67") (name "unconnected-(U6-IO12-Pad14)") (class "Default")
      (node (ref "U6") (pin "14") (pinfunction "IO12_14") (pintype "unspecified+no_connect"))
    )
    (net (code "68") (name "unconnected-(U6-IO13-Pad16)") (class "Default")
      (node (ref "U6") (pin "16") (pinfunction "IO13_16") (pintype "unspecified+no_connect"))
    )
    (net (code "69") (name "unconnected-(U6-IO14-Pad13)") (class "Default")
      (node (ref "U6") (pin "13") (pinfunction "IO14_13") (pintype "unspecified+no_connect"))
    )
    (net (code "70") (name "unconnected-(U6-IO15-Pad23)") (class "Default")
      (node (ref "U6") (pin "23") (pinfunction "IO15_23") (pintype "unspecified+no_connect"))
    )
    (net (code "71") (name "unconnected-(U6-IO17-Pad28)") (class "Default")
      (node (ref "U6") (pin "28") (pinfunction "IO17_28") (pintype "unspecified+no_connect"))
    )
    (net (code "72") (name "unconnected-(U6-IO18-Pad30)") (class "Default")
      (node (ref "U6") (pin "30") (pinfunction "IO18_30") (pintype "unspecified+no_connect"))
    )
    (net (code "73") (name "unconnected-(U6-IO19-Pad31)") (class "Default")
      (node (ref "U6") (pin "31") (pinfunction "IO19_31") (pintype "unspecified+no_connect"))
    )
    (net (code "74") (name "unconnected-(U6-IO21-Pad33)") (class "Default")
      (node (ref "U6") (pin "33") (pinfunction "IO21_33") (pintype "unspecified+no_connect"))
    )
    (net (code "75") (name "unconnected-(U6-IO23-Pad37)") (class "Default")
      (node (ref "U6") (pin "37") (pinfunction "IO23_37") (pintype "unspecified+no_connect"))
    )
    (net (code "76") (name "unconnected-(U6-IO27-Pad12)") (class "Default")
      (node (ref "U6") (pin "12") (pinfunction "IO27_12") (pintype "unspecified+no_connect"))
    )
    (net (code "77") (name "unconnected-(U6-IO32-Pad8)") (class "Default")
      (node (ref "U6") (pin "8") (pinfunction "IO32_8") (pintype "unspecified+no_connect"))
    )
    (net (code "78") (name "unconnected-(U6-IO33-Pad9)") (class "Default")
      (node (ref "U6") (pin "9") (pinfunction "IO33_9") (pintype "unspecified+no_connect"))
    )
    (net (code "79") (name "unconnected-(U6-IO34-Pad6)") (class "Default")
      (node (ref "U6") (pin "6") (pinfunction "IO34_6") (pintype "unspecified+no_connect"))
    )
    (net (code "80") (name "unconnected-(U6-IO35-Pad7)") (class "Default")
      (node (ref "U6") (pin "7") (pinfunction "IO35_7") (pintype "unspecified+no_connect"))
    )
    (net (code "81") (name "unconnected-(U6-NC-Pad17)") (class "Default")
      (node (ref "U6") (pin "17") (pinfunction "NC_17") (pintype "unspecified+no_connect"))
    )
    (net (code "82") (name "unconnected-(U6-NC-Pad18)") (class "Default")
      (node (ref "U6") (pin "18") (pinfunction "NC_18") (pintype "unspecified+no_connect"))
    )
    (net (code "83") (name "unconnected-(U6-NC-Pad19)") (class "Default")
      (node (ref "U6") (pin "19") (pinfunction "NC_19") (pintype "unspecified+no_connect"))
    )
    (net (code "84") (name "unconnected-(U6-NC-Pad20)") (class "Default")
      (node (ref "U6") (pin "20") (pinfunction "NC_20") (pintype "unspecified+no_connect"))
    )
    (net (code "85") (name "unconnected-(U6-NC-Pad21)") (class "Default")
      (node (ref "U6") (pin "21") (pinfunction "NC_21") (pintype "unspecified+no_connect"))
    )
    (net (code "86") (name "unconnected-(U6-NC-Pad22)") (class "Default")
      (node (ref "U6") (pin "22") (pinfunction "NC_22") (pintype "unspecified+no_connect"))
    )
    (net (code "87") (name "unconnected-(U6-NC-Pad32)") (class "Default")
      (node (ref "U6") (pin "32") (pinfunction "NC_32") (pintype "unspecified+no_connect"))
    )
    (net (code "88") (name "unconnected-(U6-SENSOR_VN-Pad5)") (class "Default")
      (node (ref "U6") (pin "5") (pinfunction "SENSOR_VN_5") (pintype "unspecified+no_connect"))
    )
    (net (code "89") (name "unconnected-(U6-SENSOR_VP-Pad4)") (class "Default")
      (node (ref "U6") (pin "4") (pinfunction "SENSOR_VP_4") (pintype "unspecified+no_connect"))
    )
    (net (code "90") (name "unconnected-(U7-SCK-Pad12)") (class "Default")
      (node (ref "U7") (pin "12") (pinfunction "SCK_12") (pintype "input+no_connect"))
    )
    (net (code "91") (name "unconnected-(USBC1-SBU1-PadA8)") (class "Default")
      (node (ref "USBC1") (pin "A8") (pinfunction "SBU1_A8") (pintype "unspecified+no_connect"))
    )
    (net (code "92") (name "unconnected-(USBC1-SBU2-PadB8)") (class "Default")
      (node (ref "USBC1") (pin "B8") (pinfunction "SBU2_B8") (pintype "unspecified+no_connect"))
    )
  )
)
